# 5V_REG.net
KiCad netlist of a schematic drawn in Altium Designer
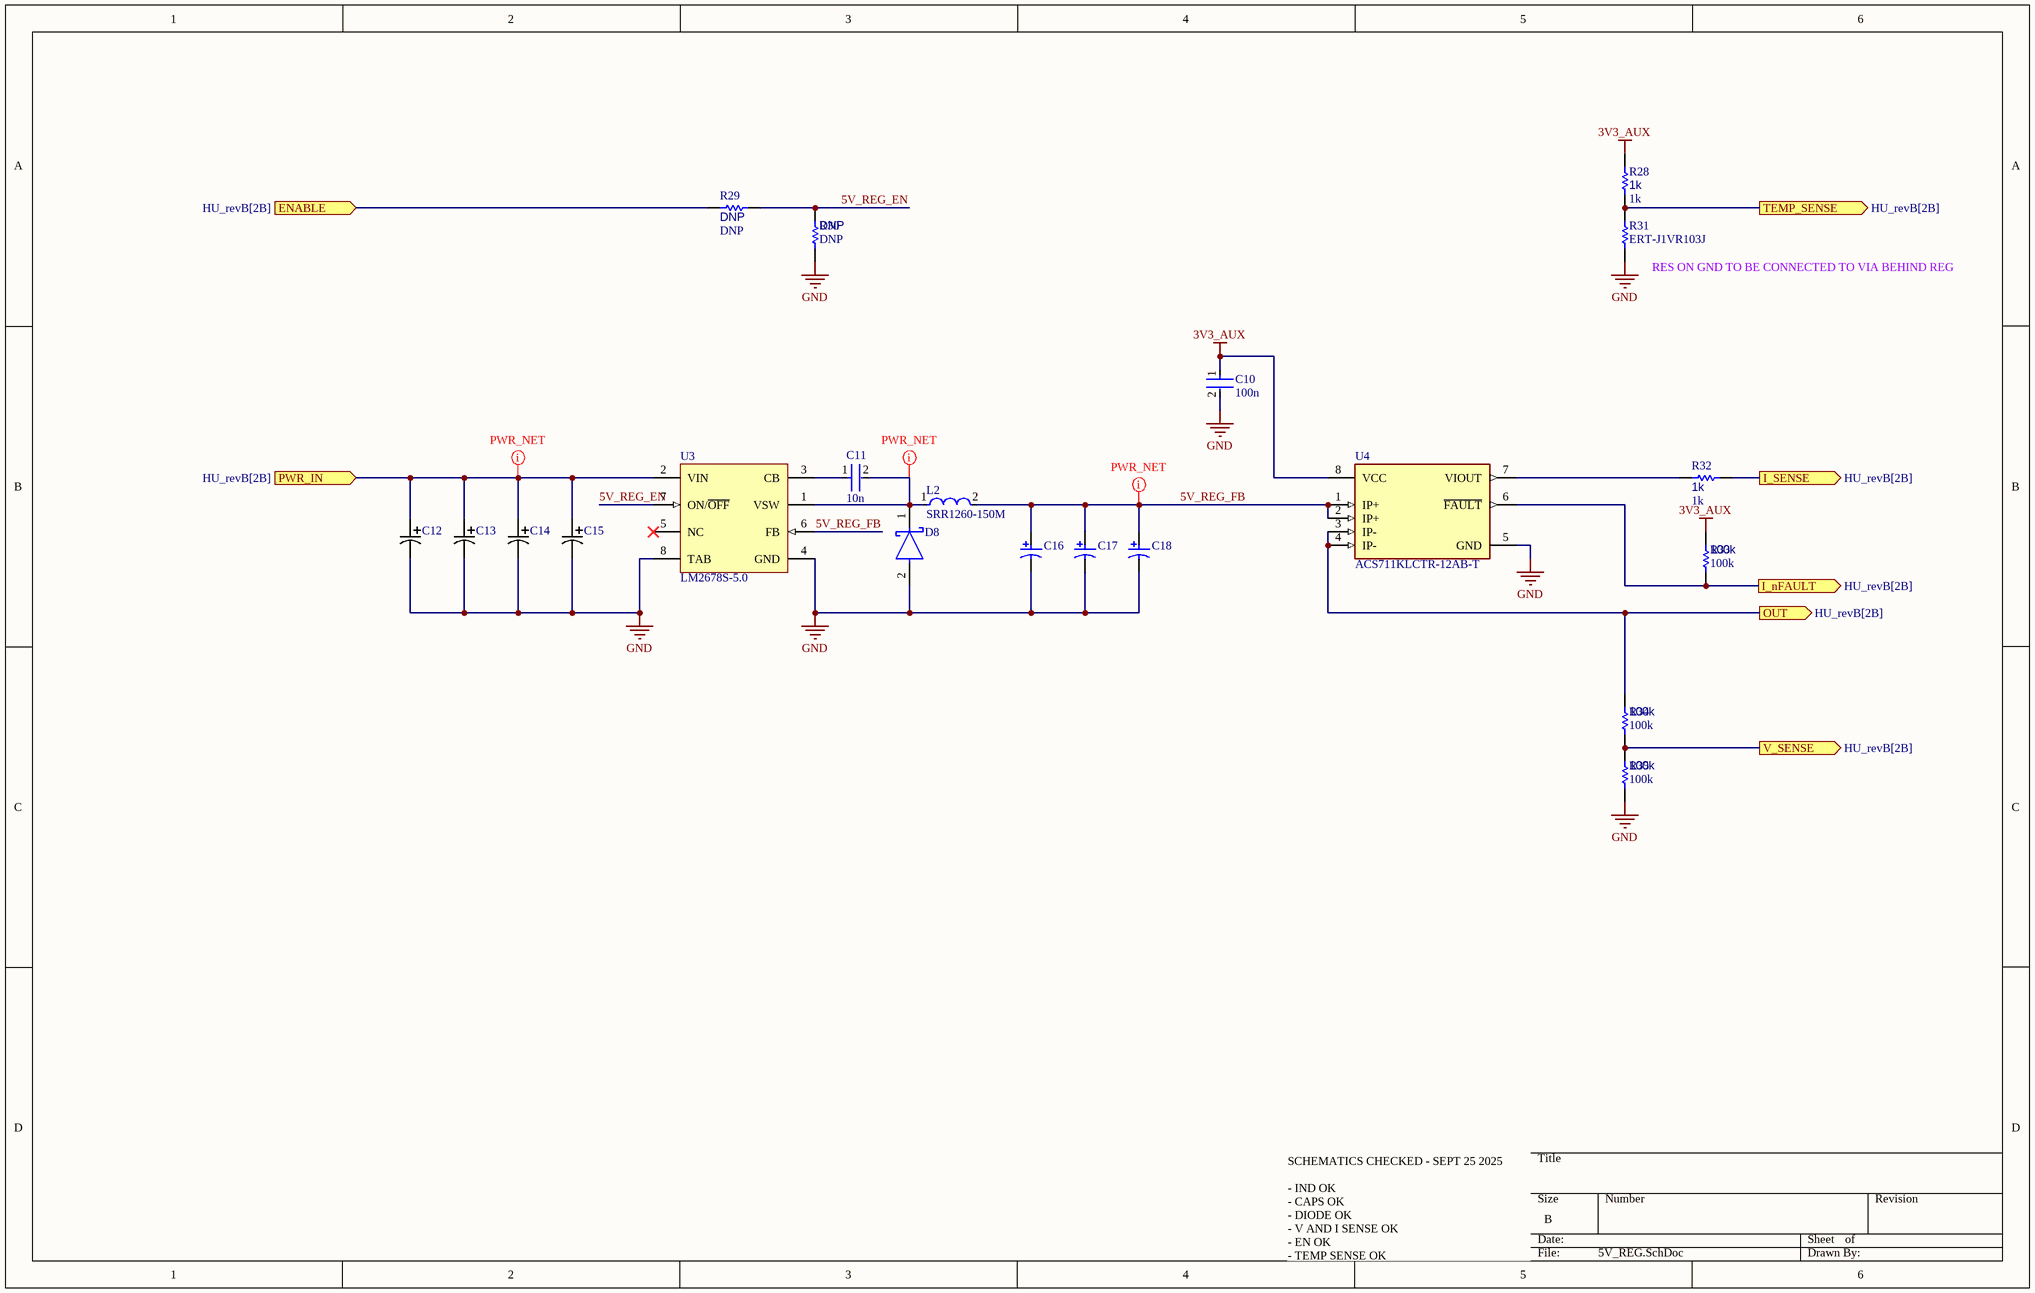
[diagram p0: 5V_REG.SchDoc]

(export (version "E")
  (design (tool "Eeschema 10.0.6"))
  (components
    (comp (ref "C10")
      (value "100n")
      (footprint "FP-0402-L_1_0_0_05-W_0_5-IPC_A")
      (description "LARGE PADS, 0402 CAP, CHANGE COMMENT TO MATCH REAL P/N")
      (libsource (lib "Space Concordia") (part "b4654b650e69147ec39a6b967a45e02"))
    )
    (comp (ref "C11")
      (value "10n")
      (footprint "FP-0402-L_1_0_0_05-W_0_5-IPC_A")
      (description "LARGE PADS, 0402 CAP, CHANGE COMMENT TO MATCH REAL P/N")
      (libsource (lib "Space Concordia") (part "b4654b650e69147ec39a6b967a45e02"))
    )
    (comp (ref "C12")
      (value "T495D106M035ATE260")
      (footprint "T495D106M035ATE260-Footprint-1")
      (fields (field (name "TOLERANCE") "20%"))
      (libsource (lib "Space Concordia") (part "T495D106M035ATE260"))
    )
    (comp (ref "C13")
      (value "T495D106M035ATE260")
      (footprint "T495D106M035ATE260-Footprint-1")
      (fields (field (name "TOLERANCE") "20%"))
      (libsource (lib "Space Concordia") (part "T495D106M035ATE260"))
    )
    (comp (ref "C14")
      (value "T495D106M035ATE260")
      (footprint "T495D106M035ATE260-Footprint-1")
      (fields (field (name "TOLERANCE") "20%"))
      (libsource (lib "Space Concordia") (part "T495D106M035ATE260"))
    )
    (comp (ref "C15")
      (value "T495D106M035ATE260")
      (footprint "T495D106M035ATE260-Footprint-1")
      (fields (field (name "TOLERANCE") "20%"))
      (libsource (lib "Space Concordia") (part "T495D106M035ATE260"))
    )
    (comp (ref "C16")
      (value "T495D157K010ATE100")
      (footprint "KEMT-T495-D_L")
      (description "Capacitor, Tantalum, 150 uF, +/- 10%, 10 V, -55 to 125 degC, 2-Pin SMD, RoHS, Tape and Reel")
      (fields (field (name "MANUFACTURER") "Kemet"))
      (libsource (lib "Altium Content Vault") (part "CAP-P-2"))
    )
    (comp (ref "C17")
      (value "T495D157K010ATE100")
      (footprint "KEMT-T495-D_L")
      (description "Capacitor, Tantalum, 150 uF, +/- 10%, 10 V, -55 to 125 degC, 2-Pin SMD, RoHS, Tape and Reel")
      (fields (field (name "MANUFACTURER") "Kemet"))
      (libsource (lib "Altium Content Vault") (part "CAP-P-2"))
    )
    (comp (ref "C18")
      (value "T495D157K010ATE100")
      (footprint "KEMT-T495-D_L")
      (description "Capacitor, Tantalum, 150 uF, +/- 10%, 10 V, -55 to 125 degC, 2-Pin SMD, RoHS, Tape and Reel")
      (fields (field (name "MANUFACTURER") "Kemet"))
      (libsource (lib "Altium Content Vault") (part "CAP-P-2"))
    )
    (comp (ref "D8")
      (value "B540C-13-F")
      (footprint "FP-SMC-MFG")
      (description "DIODE SCHOTTKY 40V 5A SMC")
      (fields
        (field (name "OCTOPART") "https://octopart.com/b540c-13-f-diodes+inc.-325873")
        (field (name "MANUFACTURER") "Diodes Inc.")
      )
      (libsource (lib "Altium Content Vault") (part "1d6ec82d83fb6aee721767c19dac4b9"))
    )
    (comp (ref "L2")
      (value "SRR1260-150M")
      (footprint "FP-SRR1260-MFG")
      (description "FIXED IND 15UH 5A 27 MOHM SMD")
      (fields (field (name "TOLERANCE") "20%"))
      (libsource (lib "Altium Content Vault") (part "725321dda6339637d4d059423bc1c3c"))
    )
    (comp (ref "R28")
      (value "1k")
      (footprint "R0603B")
      (description "Resistor")
      (fields (field (name "ALTIUM_VALUE") "1k"))
      (libsource (lib "Space Concordia") (part "Resistor"))
    )
    (comp (ref "R29")
      (value "DNP")
      (footprint "R0603B")
      (description "Resistor")
      (fields (field (name "ALTIUM_VALUE") "DNP"))
      (libsource (lib "Space Concordia") (part "Resistor"))
    )
    (comp (ref "R30")
      (value "DNP")
      (footprint "R0603B")
      (description "Resistor")
      (fields (field (name "ALTIUM_VALUE") "DNP"))
      (libsource (lib "Space Concordia") (part "Resistor"))
    )
    (comp (ref "R31")
      (value "ERT-J1VR103J")
      (footprint "RESC1608X90X30ML15T20")
      (fields (field (name "MANUFACTURER") "Panasonic"))
      (libsource (lib "Altium Content Vault") (part "RES"))
    )
    (comp (ref "R32")
      (value "1k")
      (footprint "R0603B")
      (description "Resistor")
      (fields (field (name "ALTIUM_VALUE") "1k"))
      (libsource (lib "Space Concordia") (part "Resistor"))
    )
    (comp (ref "R33")
      (value "100k")
      (footprint "R0603B")
      (description "Resistor")
      (fields (field (name "ALTIUM_VALUE") "100k"))
      (libsource (lib "Space Concordia") (part "Resistor"))
    )
    (comp (ref "R34")
      (value "100k")
      (footprint "R0603B")
      (description "Resistor")
      (fields (field (name "ALTIUM_VALUE") "100k"))
      (libsource (lib "Space Concordia") (part "Resistor"))
    )
    (comp (ref "R35")
      (value "100k")
      (footprint "R0603B")
      (description "Resistor")
      (fields (field (name "ALTIUM_VALUE") "100k"))
      (libsource (lib "Space Concordia") (part "Resistor"))
    )
    (comp (ref "U3")
      (value "LM2678S-5.0")
      (footprint "KTW0007B_N")
      (description "SIMPLE SWITCHER® High Efficiency 5A Step-Down Voltage Regulator, 7-pin TO-263")
      (fields (field (name "MANUFACTURER") "Texas Instruments"))
      (libsource (lib "Altium Content Vault") (part "PM-REG-LM2678S"))
    )
    (comp (ref "U4")
      (value "ACS711KLCTR-12AB-T")
      (footprint "FP-LC-8-IPC_C")
      (description "SENSOR CURRENT HALL 12.5A AC/DC")
      (libsource (lib "Altium Content Vault") (part "b5e82308d4912bad35d89a98a7a92f9"))
    )
  )
  (nets
    (net (code "1") (name "/5V_REG_EN") (class "Default")
      (node (ref "R29") (pin "1") (pinfunction "1_1") (pintype "passive"))
      (node (ref "R30") (pin "2") (pinfunction "2_2") (pintype "passive"))
      (node (ref "U3") (pin "7") (pinfunction "ON/~{OFF}_7") (pintype "input"))
    )
    (net (code "2") (name "/5V_REG_FB") (class "Default")
      (node (ref "C16") (pin "1") (pinfunction "1_1") (pintype "passive"))
      (node (ref "C17") (pin "1") (pinfunction "1_1") (pintype "passive"))
      (node (ref "C18") (pin "1") (pinfunction "1_1") (pintype "passive"))
      (node (ref "L2") (pin "2") (pinfunction "2_2") (pintype "passive"))
      (node (ref "U3") (pin "6") (pinfunction "FB_6") (pintype "input"))
      (node (ref "U4") (pin "1") (pinfunction "IP+_1") (pintype "input"))
      (node (ref "U4") (pin "2") (pinfunction "IP+_2") (pintype "input"))
    )
    (net (code "3") (name "/ENABLE") (class "Default")
      (node (ref "R29") (pin "2") (pinfunction "2_2") (pintype "passive"))
    )
    (net (code "4") (name "/I_SENSE") (class "Default")
      (node (ref "R32") (pin "1") (pinfunction "1_1") (pintype "passive"))
    )
    (net (code "5") (name "/I_nFAULT") (class "Default")
      (node (ref "R33") (pin "1") (pinfunction "1_1") (pintype "passive"))
      (node (ref "U4") (pin "6") (pinfunction "~{FAULT}_6") (pintype "output"))
    )
    (net (code "6") (name "/OUT") (class "Default")
      (node (ref "R34") (pin "2") (pinfunction "2_2") (pintype "passive"))
      (node (ref "U4") (pin "3") (pinfunction "IP-_3") (pintype "input"))
      (node (ref "U4") (pin "4") (pinfunction "IP-_4") (pintype "input"))
    )
    (net (code "7") (name "/PWR_IN") (class "Default")
      (node (ref "C12") (pin "1") (pinfunction "1_1") (pintype "passive"))
      (node (ref "C13") (pin "1") (pinfunction "1_1") (pintype "passive"))
      (node (ref "C14") (pin "1") (pinfunction "1_1") (pintype "passive"))
      (node (ref "C15") (pin "1") (pinfunction "1_1") (pintype "passive"))
      (node (ref "U3") (pin "2") (pinfunction "VIN_2") (pintype "power_in"))
    )
    (net (code "8") (name "/TEMP_SENSE") (class "Default")
      (node (ref "R28") (pin "2") (pinfunction "2_2") (pintype "passive"))
      (node (ref "R31") (pin "2") (pinfunction "2_2") (pintype "passive"))
    )
    (net (code "9") (name "/V_SENSE") (class "Default")
      (node (ref "R34") (pin "1") (pinfunction "1_1") (pintype "passive"))
      (node (ref "R35") (pin "2") (pinfunction "2_2") (pintype "passive"))
    )
    (net (code "10") (name "3V3_AUX") (class "Default")
      (node (ref "C10") (pin "1") (pinfunction "1_1") (pintype "passive"))
      (node (ref "R28") (pin "1") (pinfunction "1_1") (pintype "passive"))
      (node (ref "R33") (pin "2") (pinfunction "2_2") (pintype "passive"))
      (node (ref "U4") (pin "8") (pinfunction "VCC_8") (pintype "power_in"))
    )
    (net (code "11") (name "GND") (class "Default")
      (node (ref "C10") (pin "2") (pinfunction "2_2") (pintype "passive"))
      (node (ref "C12") (pin "2") (pinfunction "2_2") (pintype "passive"))
      (node (ref "C13") (pin "2") (pinfunction "2_2") (pintype "passive"))
      (node (ref "C14") (pin "2") (pinfunction "2_2") (pintype "passive"))
      (node (ref "C15") (pin "2") (pinfunction "2_2") (pintype "passive"))
      (node (ref "C16") (pin "2") (pinfunction "2_2") (pintype "passive"))
      (node (ref "C17") (pin "2") (pinfunction "2_2") (pintype "passive"))
      (node (ref "C18") (pin "2") (pinfunction "2_2") (pintype "passive"))
      (node (ref "D8") (pin "2") (pinfunction "A_2") (pintype "passive"))
      (node (ref "R30") (pin "1") (pinfunction "1_1") (pintype "passive"))
      (node (ref "R31") (pin "1") (pinfunction "1_1") (pintype "passive"))
      (node (ref "R35") (pin "1") (pinfunction "1_1") (pintype "passive"))
      (node (ref "U3") (pin "4") (pinfunction "GND_4") (pintype "power_in"))
      (node (ref "U3") (pin "8") (pinfunction "TAB_8") (pintype "power_in"))
      (node (ref "U4") (pin "5") (pinfunction "GND_5") (pintype "power_in"))
    )
    (net (code "12") (name "Net-(D8-C)") (class "Default")
      (node (ref "C11") (pin "2") (pinfunction "2_2") (pintype "passive"))
      (node (ref "D8") (pin "1") (pinfunction "C_1") (pintype "passive"))
      (node (ref "L2") (pin "1") (pinfunction "1_1") (pintype "passive"))
      (node (ref "U3") (pin "1") (pinfunction "VSW_1") (pintype "power_in"))
    )
    (net (code "13") (name "Net-(U3-CB)") (class "Default")
      (node (ref "C11") (pin "1") (pinfunction "1_1") (pintype "passive"))
      (node (ref "U3") (pin "3") (pinfunction "CB_3") (pintype "passive"))
    )
    (net (code "14") (name "Net-(U4-VIOUT)") (class "Default")
      (node (ref "R32") (pin "2") (pinfunction "2_2") (pintype "passive"))
      (node (ref "U4") (pin "7") (pinfunction "VIOUT_7") (pintype "output"))
    )
    (net (code "15") (name "unconnected-(U3-NC-Pad5)") (class "Default")
      (node (ref "U3") (pin "5") (pinfunction "NC_5") (pintype "passive+no_connect"))
    )
  )
)
